# schema_moteur.net
KiCad netlist of a schematic drawn in Altium Designer
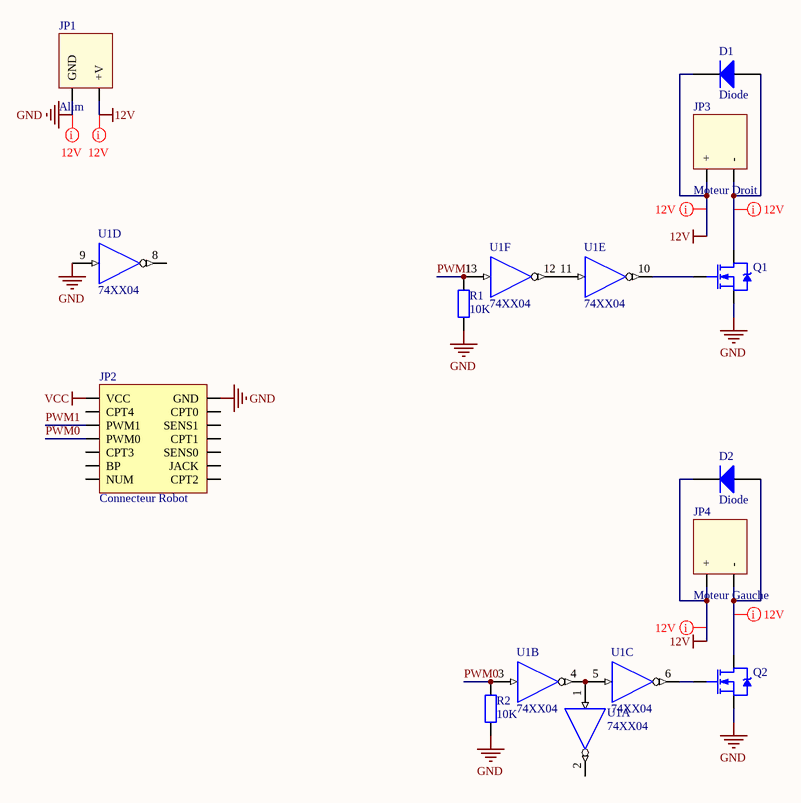
[diagram p0: schema_moteur.SchDoc]

(export (version "E")
  (design (tool "Eeschema 10.0.6"))
  (components
    (comp (ref "D1")
      (value "Diode")
      (footprint "DO-15")
      (description "Diode Générique")
      (fields (field (name "PUBLISHER") "Altium Limited"))
      (libsource (lib "GEII1") (part "Diode"))
    )
    (comp (ref "D2")
      (value "Diode")
      (footprint "DO-15")
      (description "Diode Générique")
      (fields (field (name "PUBLISHER") "Altium Limited"))
      (libsource (lib "GEII1") (part "Diode"))
    )
    (comp (ref "JP1")
      (value "Alim")
      (footprint "Miniconnect 2pts")
      (description "Connecteur d'alimentation")
      (fields
        (field (name "MANUFACTURER") "IMO PRECISION CONTROLS")
        (field (name "MANUFACTURER PART NUMBER") "21.95MH/2")
      )
      (libsource (lib "GEII1") (part "Connecteur Alimentation"))
    )
    (comp (ref "JP2")
      (value "Connecteur Robot")
      (footprint "HE10 2x7")
      (description "Connecteurr pour robot S1")
      (libsource (lib "GEII1") (part "HE10 Robot"))
    )
    (comp (ref "JP3")
      (value "Moteur Droit")
      (footprint "Miniconnect 2pts")
      (description "Connecteur de puissance 2 pts")
      (fields
        (field (name "MANUFACTURER") "PHOENIX CONTACT")
        (field (name "MANUFACTURER PART NUMBER") "1757242")
      )
      (libsource (lib "GEII1") (part "Miniconnect"))
    )
    (comp (ref "JP4")
      (value "Moteur Gauche")
      (footprint "Miniconnect 2pts")
      (description "Connecteur de puissance 2 pts")
      (fields
        (field (name "MANUFACTURER") "PHOENIX CONTACT")
        (field (name "MANUFACTURER PART NUMBER") "1757242")
      )
      (libsource (lib "GEII1") (part "Miniconnect"))
    )
    (comp (ref "Q1")
      (value "IRL510")
      (footprint "TO220_FLAT")
      (description "HEXFET N-Channel Power MOSFET")
      (fields
        (field (name "MANUFACTURER") "VISHAY FORMERLY I.R.")
        (field (name "MANUFACTURER PART NUMBER") "IRL510PBF")
        (field (name "PUBLISHER") "Altium Limited")
      )
      (libsource (lib "GEII1") (part "IRL510"))
    )
    (comp (ref "Q2")
      (value "IRL510")
      (footprint "TO220_FLAT")
      (description "HEXFET N-Channel Power MOSFET")
      (fields
        (field (name "MANUFACTURER") "VISHAY FORMERLY I.R.")
        (field (name "MANUFACTURER PART NUMBER") "IRL510PBF")
        (field (name "PUBLISHER") "Altium Limited")
      )
      (libsource (lib "GEII1") (part "IRL510"))
    )
    (comp (ref "R1")
      (value "10K")
      (footprint "Axial_5")
      (description "Resistance")
      (fields (field (name "PUBLISHER") "Altium Limited"))
      (libsource (lib "GEII1") (part "Res"))
    )
    (comp (ref "R2")
      (value "10K")
      (footprint "Axial_5")
      (description "Resistance")
      (fields (field (name "PUBLISHER") "Altium Limited"))
      (libsource (lib "GEII1") (part "Res"))
    )
    (comp (ref "U1")
      (value "74XX04")
      (footprint "SOIC_14")
      (description "Hex Inverter")
      (fields (field (name "PUBLISHER") "Altium Limited"))
      (libsource (lib "GEII1") (part "74XX04"))
    )
  )
  (nets
    (net (code "1") (name "/PWM0") (class "Default")
      (node (ref "JP2") (pin "7") (pinfunction "PWM0_7") (pintype "passive"))
      (node (ref "R2") (pin "2") (pinfunction "2_2") (pintype "passive"))
      (node (ref "U1") (pin "3") (pinfunction "A_3") (pintype "input"))
    )
    (net (code "2") (name "/PWM1") (class "Default")
      (node (ref "JP2") (pin "5") (pinfunction "PWM1_5") (pintype "passive"))
      (node (ref "R1") (pin "2") (pinfunction "2_2") (pintype "passive"))
      (node (ref "U1") (pin "13") (pinfunction "A_13") (pintype "input"))
    )
    (net (code "3") (name "12V") (class "Default")
      (node (ref "D1") (pin "1") (pinfunction "K_1") (pintype "passive"))
      (node (ref "D2") (pin "1") (pinfunction "K_1") (pintype "passive"))
      (node (ref "JP1") (pin "2") (pinfunction "+V_2") (pintype "passive"))
      (node (ref "JP3") (pin "2") (pinfunction "+_2") (pintype "passive"))
      (node (ref "JP4") (pin "2") (pinfunction "+_2") (pintype "passive"))
    )
    (net (code "4") (name "GND") (class "Default")
      (node (ref "JP1") (pin "1") (pinfunction "GND_1") (pintype "passive"))
      (node (ref "JP2") (pin "2") (pinfunction "GND_2") (pintype "passive"))
      (node (ref "Q1") (pin "3") (pinfunction "S_3") (pintype "passive"))
      (node (ref "Q2") (pin "3") (pinfunction "S_3") (pintype "passive"))
      (node (ref "R1") (pin "1") (pinfunction "1_1") (pintype "passive"))
      (node (ref "R2") (pin "1") (pinfunction "1_1") (pintype "passive"))
      (node (ref "U1") (pin "7") (pinfunction "GND_7") (pintype "power_in"))
      (node (ref "U1") (pin "9") (pinfunction "A_9") (pintype "input"))
    )
    (net (code "5") (name "Net-(D1-A)") (class "Default")
      (node (ref "D1") (pin "2") (pinfunction "A_2") (pintype "passive"))
      (node (ref "JP3") (pin "1") (pinfunction "-_1") (pintype "passive"))
      (node (ref "Q1") (pin "2") (pinfunction "D_2") (pintype "passive"))
    )
    (net (code "6") (name "Net-(D2-A)") (class "Default")
      (node (ref "D2") (pin "2") (pinfunction "A_2") (pintype "passive"))
      (node (ref "JP4") (pin "1") (pinfunction "-_1") (pintype "passive"))
      (node (ref "Q2") (pin "2") (pinfunction "D_2") (pintype "passive"))
    )
    (net (code "7") (name "Net-(Q1-G)") (class "Default")
      (node (ref "Q1") (pin "1") (pinfunction "G_1") (pintype "passive"))
      (node (ref "U1") (pin "10") (pinfunction "Y_10") (pintype "output"))
    )
    (net (code "8") (name "Net-(Q2-G)") (class "Default")
      (node (ref "Q2") (pin "1") (pinfunction "G_1") (pintype "passive"))
      (node (ref "U1") (pin "6") (pinfunction "Y_6") (pintype "output"))
    )
    (net (code "9") (name "Net-(U1A-A)") (class "Default")
      (node (ref "U1") (pin "1") (pinfunction "A_1") (pintype "input"))
      (node (ref "U1") (pin "4") (pinfunction "Y_4") (pintype "output"))
      (node (ref "U1") (pin "5") (pinfunction "A_5") (pintype "input"))
    )
    (net (code "10") (name "Net-(U1E-A)") (class "Default")
      (node (ref "U1") (pin "11") (pinfunction "A_11") (pintype "input"))
      (node (ref "U1") (pin "12") (pinfunction "Y_12") (pintype "output"))
    )
    (net (code "11") (name "VCC") (class "Default")
      (node (ref "JP2") (pin "1") (pinfunction "VCC_1") (pintype "passive"))
      (node (ref "U1") (pin "14") (pinfunction "VCC_14") (pintype "power_in"))
    )
    (net (code "12") (name "unconnected-(JP2-BP-Pad11)") (class "Default")
      (node (ref "JP2") (pin "11") (pinfunction "BP_11") (pintype "passive"))
    )
    (net (code "13") (name "unconnected-(JP2-CPT0-Pad4)") (class "Default")
      (node (ref "JP2") (pin "4") (pinfunction "CPT0_4") (pintype "passive"))
    )
    (net (code "14") (name "unconnected-(JP2-CPT1-Pad8)") (class "Default")
      (node (ref "JP2") (pin "8") (pinfunction "CPT1_8") (pintype "passive"))
    )
    (net (code "15") (name "unconnected-(JP2-CPT2-Pad14)") (class "Default")
      (node (ref "JP2") (pin "14") (pinfunction "CPT2_14") (pintype "passive"))
    )
    (net (code "16") (name "unconnected-(JP2-CPT3-Pad9)") (class "Default")
      (node (ref "JP2") (pin "9") (pinfunction "CPT3_9") (pintype "passive"))
    )
    (net (code "17") (name "unconnected-(JP2-CPT4-Pad3)") (class "Default")
      (node (ref "JP2") (pin "3") (pinfunction "CPT4_3") (pintype "passive"))
    )
    (net (code "18") (name "unconnected-(JP2-JACK-Pad12)") (class "Default")
      (node (ref "JP2") (pin "12") (pinfunction "JACK_12") (pintype "passive"))
    )
    (net (code "19") (name "unconnected-(JP2-NUM-Pad13)") (class "Default")
      (node (ref "JP2") (pin "13") (pinfunction "NUM_13") (pintype "passive"))
    )
    (net (code "20") (name "unconnected-(JP2-SENS0-Pad10)") (class "Default")
      (node (ref "JP2") (pin "10") (pinfunction "SENS0_10") (pintype "passive"))
    )
    (net (code "21") (name "unconnected-(JP2-SENS1-Pad6)") (class "Default")
      (node (ref "JP2") (pin "6") (pinfunction "SENS1_6") (pintype "passive"))
    )
    (net (code "22") (name "unconnected-(U1A-Y-Pad2)") (class "Default")
      (node (ref "U1") (pin "2") (pinfunction "Y_2") (pintype "output"))
    )
    (net (code "23") (name "unconnected-(U1D-Y-Pad8)") (class "Default")
      (node (ref "U1") (pin "8") (pinfunction "Y_8") (pintype "output"))
    )
  )
)
